# TeensyLED_15041702.net
KiCad netlist of a schematic drawn in EAGLE
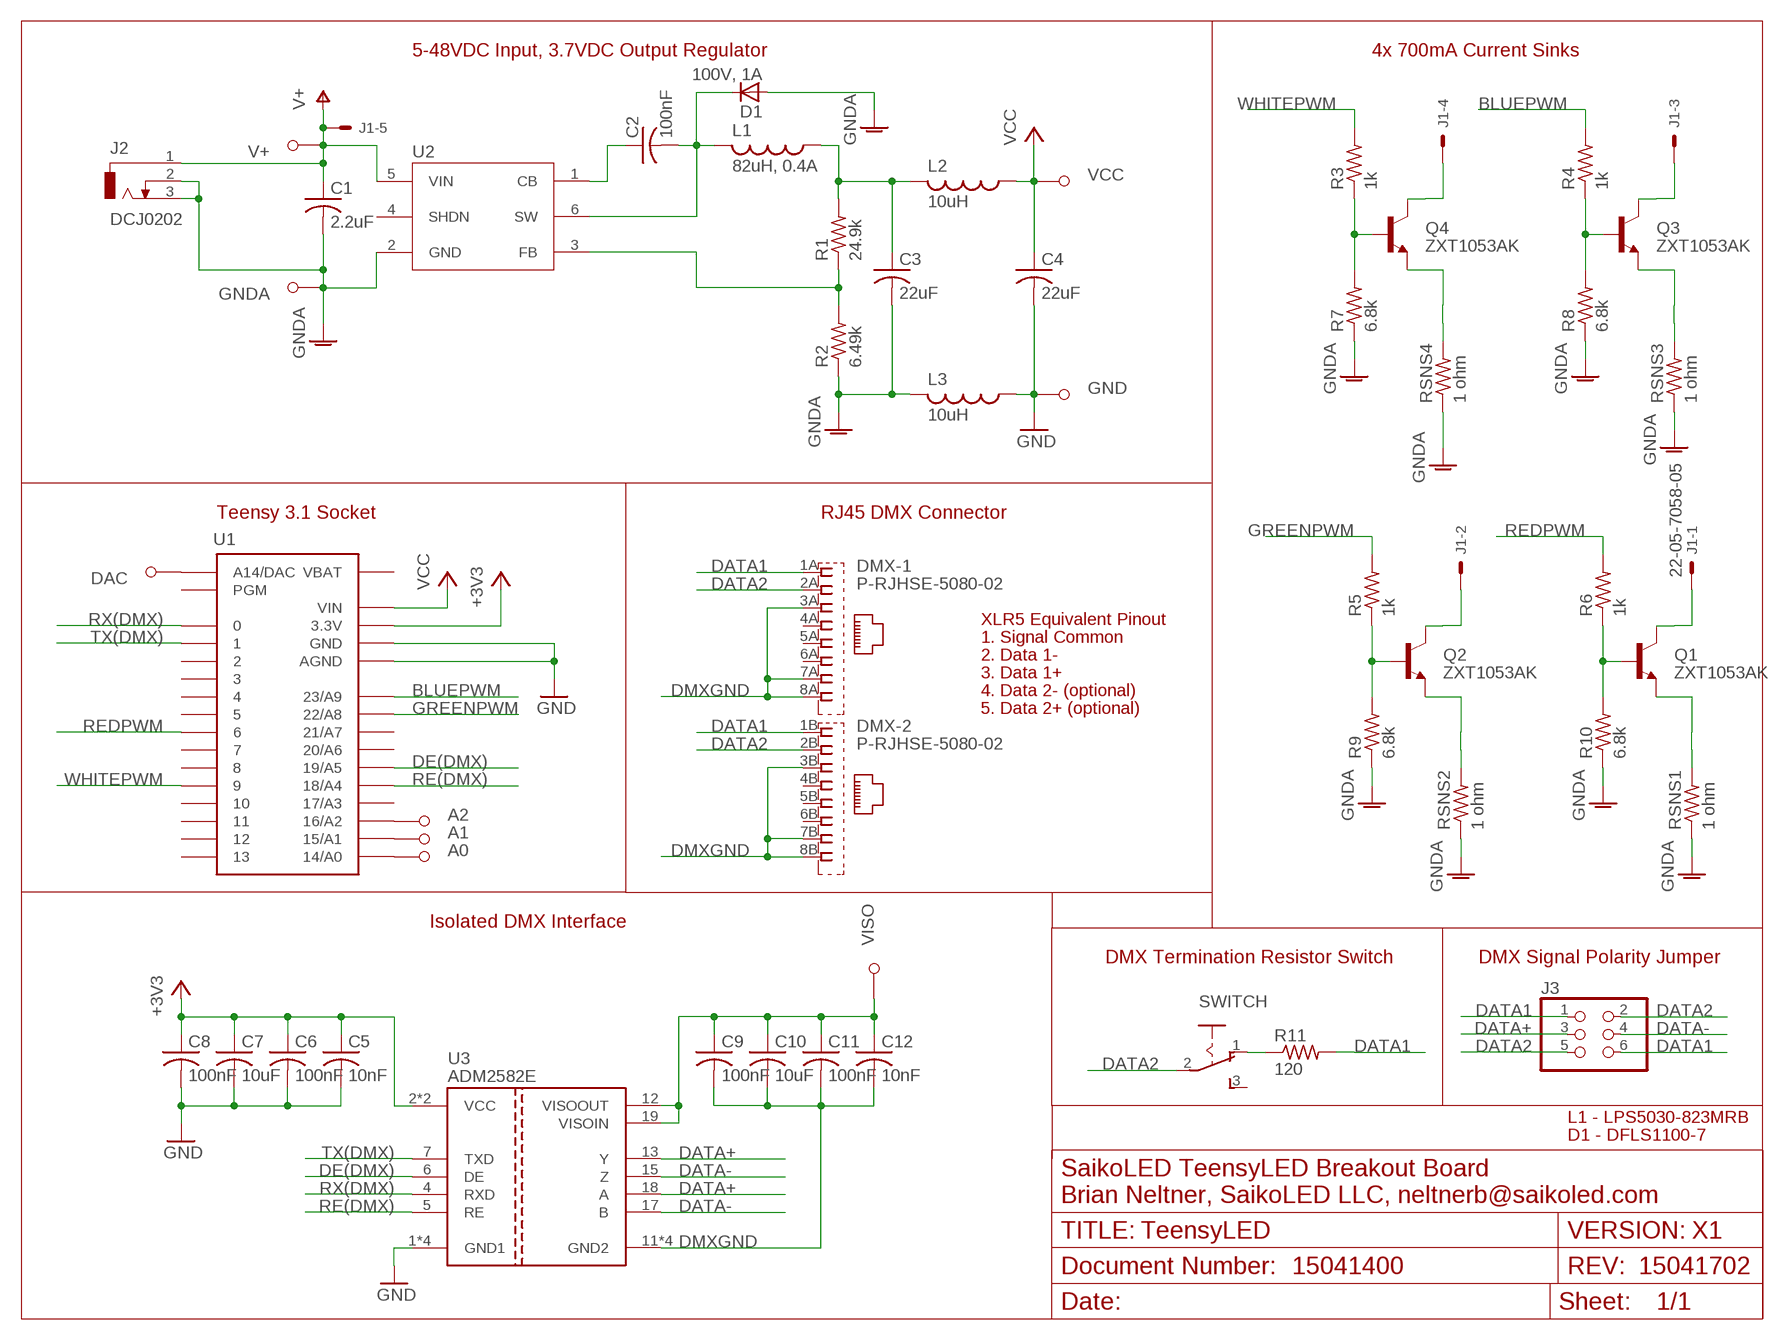
[diagram p0: schematic, sheet 1]

(export (version "E")
  (design (tool "Eeschema 10.0.6"))
  (components
    (comp (ref "A0")
      (value "5016")
      (footprint "eagle-import:5016")
      (libsource (lib "eagle-import") (part "5016"))
    )
    (comp (ref "A1")
      (value "5016")
      (footprint "eagle-import:5016")
      (libsource (lib "eagle-import") (part "5016"))
    )
    (comp (ref "A2")
      (value "5016")
      (footprint "eagle-import:5016")
      (libsource (lib "eagle-import") (part "5016"))
    )
    (comp (ref "C1")
      (value "2.2uF")
      (footprint "eagle-import:C1210K")
      (libsource (lib "eagle-import") (part "C-USC1210K"))
    )
    (comp (ref "C2")
      (value "100nF")
      (footprint "eagle-import:C0805K")
      (libsource (lib "eagle-import") (part "C-USC0805K"))
    )
    (comp (ref "C3")
      (value "22uF")
      (footprint "eagle-import:C0805K")
      (fields (field (name "MF") "Multicomp Passives") (field (name "MPN") "MCLV4R7M1HB-0513-RH"))
      (libsource (lib "eagle-import") (part "C-USC0805K"))
    )
    (comp (ref "C4")
      (value "22uF")
      (footprint "eagle-import:C0805K")
      (libsource (lib "eagle-import") (part "C-USC0805K"))
    )
    (comp (ref "C5")
      (value "10nF")
      (footprint "eagle-import:C0402PRO")
      (libsource (lib "eagle-import") (part "C-USC0402PRO"))
    )
    (comp (ref "C6")
      (value "100nF")
      (footprint "eagle-import:C0402PRO")
      (libsource (lib "eagle-import") (part "C-USC0402PRO"))
    )
    (comp (ref "C7")
      (value "10uF")
      (footprint "eagle-import:C0402PRO")
      (libsource (lib "eagle-import") (part "C-USC0402PRO"))
    )
    (comp (ref "C8")
      (value "100nF")
      (footprint "eagle-import:C0402PRO")
      (libsource (lib "eagle-import") (part "C-USC0402PRO"))
    )
    (comp (ref "C9")
      (value "100nF")
      (footprint "eagle-import:C0402PRO")
      (libsource (lib "eagle-import") (part "C-USC0402PRO"))
    )
    (comp (ref "C10")
      (value "10uF")
      (footprint "eagle-import:C0402PRO")
      (libsource (lib "eagle-import") (part "C-USC0402PRO"))
    )
    (comp (ref "C11")
      (value "100nF")
      (footprint "eagle-import:C0402PRO")
      (libsource (lib "eagle-import") (part "C-USC0402PRO"))
    )
    (comp (ref "C12")
      (value "10nF")
      (footprint "eagle-import:C0402PRO")
      (libsource (lib "eagle-import") (part "C-USC0402PRO"))
    )
    (comp (ref "D1")
      (value "100V, 1A")
      (footprint "eagle-import:DFLS1100")
      (libsource (lib "eagle-import") (part "DFLS1100"))
    )
    (comp (ref "DAC")
      (value "5016")
      (footprint "eagle-import:5016")
      (libsource (lib "eagle-import") (part "5016"))
    )
    (comp (ref "DMX")
      (value "P-RJHSE-5080-02")
      (footprint "eagle-import:P-RJHSE-5080-02")
      (libsource (lib "eagle-import") (part "P-RJHSE-5080-02"))
    )
    (comp (ref "FRAME1")
      (value "LETTER_L")
      (footprint "eagle-import:PCBINFO")
      (libsource (lib "eagle-import") (part "LETTER_L"))
    )
    (comp (ref "GND")
      (value "5016")
      (footprint "eagle-import:5016")
      (libsource (lib "eagle-import") (part "5016"))
    )
    (comp (ref "GNDA")
      (value "5016")
      (footprint "eagle-import:5016")
      (libsource (lib "eagle-import") (part "5016"))
    )
    (comp (ref "J1")
      (value "22-05-7058-05")
      (footprint "eagle-import:7395-05")
      (libsource (lib "eagle-import") (part "22-?-0505-7058"))
    )
    (comp (ref "J2")
      (value "DCJ0202")
      (footprint "eagle-import:DCJ0202")
      (libsource (lib "eagle-import") (part "DCJ0202"))
    )
    (comp (ref "J3")
      (value "PINHD-2X3")
      (footprint "eagle-import:2X03")
      (libsource (lib "eagle-import") (part "PINHD-2X3"))
    )
    (comp (ref "L1")
      (value "82uH, 0.4A")
      (footprint "eagle-import:LPS5030")
      (libsource (lib "eagle-import") (part "L-US"))
    )
    (comp (ref "L2")
      (value "10uH")
      (footprint "eagle-import:L2012C")
      (libsource (lib "eagle-import") (part "rcl_L-USL2012C"))
    )
    (comp (ref "L3")
      (value "10uH")
      (footprint "eagle-import:L2012C")
      (libsource (lib "eagle-import") (part "rcl_L-USL2012C"))
    )
    (comp (ref "Q1")
      (value "ZXT1053AK")
      (footprint "eagle-import:TO252")
      (libsource (lib "eagle-import") (part "ZXT1053AK"))
    )
    (comp (ref "Q2")
      (value "ZXT1053AK")
      (footprint "eagle-import:TO252")
      (libsource (lib "eagle-import") (part "ZXT1053AK"))
    )
    (comp (ref "Q3")
      (value "ZXT1053AK")
      (footprint "eagle-import:TO252")
      (libsource (lib "eagle-import") (part "ZXT1053AK"))
    )
    (comp (ref "Q4")
      (value "ZXT1053AK")
      (footprint "eagle-import:TO252")
      (libsource (lib "eagle-import") (part "ZXT1053AK"))
    )
    (comp (ref "R1")
      (value "24.9k")
      (footprint "eagle-import:R0402PRO")
      (fields (field (name "MPN") "BLU0402-9762-BT25W"))
      (libsource (lib "eagle-import") (part "R-US_R0402PRO"))
    )
    (comp (ref "R2")
      (value "6.49k")
      (footprint "eagle-import:R0402PRO")
      (fields (field (name "MPN") "ERJ-3EKF4123V"))
      (libsource (lib "eagle-import") (part "R-US_R0402PRO"))
    )
    (comp (ref "R3")
      (value "1k")
      (footprint "eagle-import:R0402PRO")
      (libsource (lib "eagle-import") (part "R-US_R0402PRO"))
    )
    (comp (ref "R4")
      (value "1k")
      (footprint "eagle-import:R0402PRO")
      (libsource (lib "eagle-import") (part "R-US_R0402PRO"))
    )
    (comp (ref "R5")
      (value "1k")
      (footprint "eagle-import:R0402PRO")
      (libsource (lib "eagle-import") (part "R-US_R0402PRO"))
    )
    (comp (ref "R6")
      (value "1k")
      (footprint "eagle-import:R0402PRO")
      (libsource (lib "eagle-import") (part "R-US_R0402PRO"))
    )
    (comp (ref "R7")
      (value "6.8k")
      (footprint "eagle-import:R0402PRO")
      (libsource (lib "eagle-import") (part "R-US_R0402PRO"))
    )
    (comp (ref "R8")
      (value "6.8k")
      (footprint "eagle-import:R0402PRO")
      (libsource (lib "eagle-import") (part "R-US_R0402PRO"))
    )
    (comp (ref "R9")
      (value "6.8k")
      (footprint "eagle-import:R0402PRO")
      (libsource (lib "eagle-import") (part "R-US_R0402PRO"))
    )
    (comp (ref "R10")
      (value "6.8k")
      (footprint "eagle-import:R0402PRO")
      (libsource (lib "eagle-import") (part "R-US_R0402PRO"))
    )
    (comp (ref "R11")
      (value "120")
      (footprint "eagle-import:R0402PRO")
      (libsource (lib "eagle-import") (part "R-US_R0402PRO"))
    )
    (comp (ref "RSNS1")
      (value "1 ohm")
      (footprint "eagle-import:R1206")
      (libsource (lib "eagle-import") (part "R-US_R1206"))
    )
    (comp (ref "RSNS2")
      (value "1 ohm")
      (footprint "eagle-import:R1206")
      (libsource (lib "eagle-import") (part "R-US_R1206"))
    )
    (comp (ref "RSNS3")
      (value "1 ohm")
      (footprint "eagle-import:R1206")
      (libsource (lib "eagle-import") (part "R-US_R1206"))
    )
    (comp (ref "RSNS4")
      (value "1 ohm")
      (footprint "eagle-import:R1206")
      (libsource (lib "eagle-import") (part "R-US_R1206"))
    )
    (comp (ref "SWITCH")
      (value "M251")
      (footprint "eagle-import:SK-12F17-G")
      (libsource (lib "eagle-import") (part "M251"))
    )
    (comp (ref "U1")
      (value "TEENSY_3.0_BASIC")
      (footprint "eagle-import:TEENSY_3.0_BASIC")
      (libsource (lib "eagle-import") (part "TEENSY_3.0_BASIC"))
    )
    (comp (ref "U2")
      (value "LMR16006YDDCT")
      (footprint "eagle-import:DDC0006A")
      (fields
        (field (name "MANUFACTURER") "Texas Instruments")
        (field (name "PARTNUMBER") "LMR16006YDDC")
        (field (name "MF") "FARNELL")
      )
      (libsource (lib "eagle-import") (part "LMR16006YDDCT"))
    )
    (comp (ref "U3")
      (value "ADM2582E")
      (footprint "eagle-import:SO-20DW")
      (libsource (lib "eagle-import") (part "ADM2582E"))
    )
    (comp (ref "V+")
      (value "5016")
      (footprint "eagle-import:5016")
      (libsource (lib "eagle-import") (part "5016"))
    )
    (comp (ref "VCC")
      (value "5016")
      (footprint "eagle-import:5016")
      (libsource (lib "eagle-import") (part "5016"))
    )
    (comp (ref "VISO")
      (value "5016")
      (footprint "eagle-import:5016")
      (libsource (lib "eagle-import") (part "5016"))
    )
  )
  (nets
    (net (code "1") (name "+3V3") (class "Default")
      (node (ref "C5") (pin "1") (pinfunction "1_1") (pintype "passive"))
      (node (ref "C6") (pin "1") (pinfunction "1_1") (pintype "passive"))
      (node (ref "C7") (pin "1") (pinfunction "1_1") (pintype "passive"))
      (node (ref "C8") (pin "1") (pinfunction "1_1") (pintype "passive"))
      (node (ref "U1") (pin "3.3V") (pinfunction "3.3V_3.3V") (pintype "power_in"))
      (node (ref "U1") (pin "3.3V1") (pinfunction "3.3V_3.3V1") (pintype "power_in"))
      (node (ref "U3") (pin "2") (pinfunction "VCC_2") (pintype "bidirectional"))
      (node (ref "U3") (pin "8") (pinfunction "VCC_8") (pintype "bidirectional"))
    )
    (net (code "2") (name "/BLUEPWM") (class "Default")
      (node (ref "R4") (pin "2") (pinfunction "2_2") (pintype "passive"))
      (node (ref "U1") (pin "23/A9") (pinfunction "23/A9_23/A9") (pintype "bidirectional"))
    )
    (net (code "3") (name "/DATA+") (class "Default")
      (node (ref "J3") (pin "3") (pinfunction "3_3") (pintype "passive"))
      (node (ref "U3") (pin "13") (pinfunction "Y_13") (pintype "bidirectional"))
      (node (ref "U3") (pin "18") (pinfunction "A_18") (pintype "bidirectional"))
    )
    (net (code "4") (name "/DATA-") (class "Default")
      (node (ref "J3") (pin "4") (pinfunction "4_4") (pintype "passive"))
      (node (ref "U3") (pin "15") (pinfunction "Z_15") (pintype "bidirectional"))
      (node (ref "U3") (pin "17") (pinfunction "B_17") (pintype "bidirectional"))
    )
    (net (code "5") (name "/DATA1") (class "Default")
      (node (ref "DMX") (pin "1A") (pinfunction "1_1A") (pintype "passive"))
      (node (ref "DMX") (pin "1B") (pinfunction "1_1B") (pintype "passive"))
      (node (ref "J3") (pin "1") (pinfunction "1_1") (pintype "passive"))
      (node (ref "J3") (pin "6") (pinfunction "6_6") (pintype "passive"))
      (node (ref "R11") (pin "2") (pinfunction "2_2") (pintype "passive"))
    )
    (net (code "6") (name "/DATA2") (class "Default")
      (node (ref "DMX") (pin "2A") (pinfunction "2_2A") (pintype "passive"))
      (node (ref "DMX") (pin "2B") (pinfunction "2_2B") (pintype "passive"))
      (node (ref "J3") (pin "2") (pinfunction "2_2") (pintype "passive"))
      (node (ref "J3") (pin "5") (pinfunction "5_5") (pintype "passive"))
      (node (ref "SWITCH") (pin "2") (pinfunction "P_2") (pintype "passive"))
    )
    (net (code "7") (name "/DE(DMX)") (class "Default")
      (node (ref "U1") (pin "19/A5") (pinfunction "19/A5_19/A5") (pintype "bidirectional"))
      (node (ref "U3") (pin "6") (pinfunction "DE_6") (pintype "bidirectional"))
    )
    (net (code "8") (name "/DMXGND") (class "Default")
      (node (ref "C10") (pin "2") (pinfunction "2_2") (pintype "passive"))
      (node (ref "C11") (pin "2") (pinfunction "2_2") (pintype "passive"))
      (node (ref "C12") (pin "2") (pinfunction "2_2") (pintype "passive"))
      (node (ref "C9") (pin "2") (pinfunction "2_2") (pintype "passive"))
      (node (ref "DMX") (pin "3A") (pinfunction "3_3A") (pintype "passive"))
      (node (ref "DMX") (pin "3B") (pinfunction "3_3B") (pintype "passive"))
      (node (ref "DMX") (pin "7A") (pinfunction "7_7A") (pintype "passive"))
      (node (ref "DMX") (pin "7B") (pinfunction "7_7B") (pintype "passive"))
      (node (ref "DMX") (pin "8A") (pinfunction "8_8A") (pintype "passive"))
      (node (ref "DMX") (pin "8B") (pinfunction "8_8B") (pintype "passive"))
      (node (ref "U3") (pin "11") (pinfunction "GND2_11") (pintype "bidirectional"))
      (node (ref "U3") (pin "14") (pinfunction "GND2_14") (pintype "bidirectional"))
      (node (ref "U3") (pin "16") (pinfunction "GND2_16") (pintype "bidirectional"))
      (node (ref "U3") (pin "20") (pinfunction "GND2_20") (pintype "bidirectional"))
    )
    (net (code "9") (name "/GREENPWM") (class "Default")
      (node (ref "R5") (pin "2") (pinfunction "2_2") (pintype "passive"))
      (node (ref "U1") (pin "22/A8") (pinfunction "22/A8_22/A8") (pintype "bidirectional"))
    )
    (net (code "10") (name "/RE(DMX)") (class "Default")
      (node (ref "U1") (pin "18/A4") (pinfunction "18/A4_18/A4") (pintype "bidirectional"))
      (node (ref "U3") (pin "5") (pinfunction "RE_5") (pintype "bidirectional"))
    )
    (net (code "11") (name "/REDPWM") (class "Default")
      (node (ref "R6") (pin "2") (pinfunction "2_2") (pintype "passive"))
      (node (ref "U1") (pin "6") (pinfunction "6_6") (pintype "bidirectional"))
    )
    (net (code "12") (name "/RX(DMX)") (class "Default")
      (node (ref "U1") (pin "0") (pinfunction "0_0") (pintype "bidirectional"))
      (node (ref "U3") (pin "4") (pinfunction "RXD_4") (pintype "bidirectional"))
    )
    (net (code "13") (name "/TX(DMX)") (class "Default")
      (node (ref "U1") (pin "1") (pinfunction "1_1") (pintype "bidirectional"))
      (node (ref "U3") (pin "7") (pinfunction "TXD_7") (pintype "bidirectional"))
    )
    (net (code "14") (name "/VBAT") (class "Default")
      (node (ref "U1") (pin "VBAT") (pinfunction "VBAT_VBAT") (pintype "power_in"))
    )
    (net (code "15") (name "/WHITEPWM") (class "Default")
      (node (ref "R3") (pin "2") (pinfunction "2_2") (pintype "passive"))
      (node (ref "U1") (pin "9") (pinfunction "9_9") (pintype "bidirectional"))
    )
    (net (code "16") (name "GND") (class "Default")
      (node (ref "C4") (pin "2") (pinfunction "2_2") (pintype "passive"))
      (node (ref "C5") (pin "2") (pinfunction "2_2") (pintype "passive"))
      (node (ref "C6") (pin "2") (pinfunction "2_2") (pintype "passive"))
      (node (ref "C7") (pin "2") (pinfunction "2_2") (pintype "passive"))
      (node (ref "C8") (pin "2") (pinfunction "2_2") (pintype "passive"))
      (node (ref "GND") (pin "P$1") (pinfunction "P$1_P$1") (pintype "passive"))
      (node (ref "L3") (pin "1") (pinfunction "1_1") (pintype "passive"))
      (node (ref "U1") (pin "AGND") (pinfunction "AGND_AGND") (pintype "power_in"))
      (node (ref "U1") (pin "GND") (pinfunction "GND_GND") (pintype "power_in"))
      (node (ref "U1") (pin "GND1") (pinfunction "GND_GND1") (pintype "power_in"))
      (node (ref "U3") (pin "1") (pinfunction "GND1_1") (pintype "bidirectional"))
      (node (ref "U3") (pin "10") (pinfunction "GND1_10") (pintype "bidirectional"))
      (node (ref "U3") (pin "3") (pinfunction "GND1_3") (pintype "bidirectional"))
      (node (ref "U3") (pin "9") (pinfunction "GND1_9") (pintype "bidirectional"))
    )
    (net (code "17") (name "GNDA") (class "Default")
      (node (ref "C1") (pin "2") (pinfunction "2_2") (pintype "passive"))
      (node (ref "C3") (pin "2") (pinfunction "2_2") (pintype "passive"))
      (node (ref "D1") (pin "A") (pinfunction "A_A") (pintype "passive"))
      (node (ref "GNDA") (pin "P$1") (pinfunction "P$1_P$1") (pintype "passive"))
      (node (ref "J2") (pin "2") (pinfunction "2_2") (pintype "passive"))
      (node (ref "J2") (pin "3") (pinfunction "3_3") (pintype "passive"))
      (node (ref "L3") (pin "2") (pinfunction "2_2") (pintype "passive"))
      (node (ref "R10") (pin "1") (pinfunction "1_1") (pintype "passive"))
      (node (ref "R2") (pin "1") (pinfunction "1_1") (pintype "passive"))
      (node (ref "R7") (pin "1") (pinfunction "1_1") (pintype "passive"))
      (node (ref "R8") (pin "1") (pinfunction "1_1") (pintype "passive"))
      (node (ref "R9") (pin "1") (pinfunction "1_1") (pintype "passive"))
      (node (ref "RSNS1") (pin "1") (pinfunction "1_1") (pintype "passive"))
      (node (ref "RSNS2") (pin "1") (pinfunction "1_1") (pintype "passive"))
      (node (ref "RSNS3") (pin "1") (pinfunction "1_1") (pintype "passive"))
      (node (ref "RSNS4") (pin "1") (pinfunction "1_1") (pintype "passive"))
      (node (ref "U2") (pin "2") (pinfunction "GND_2") (pintype "power_in"))
    )
    (net (code "18") (name "Net-(A0-PadP$1)") (class "Default")
      (node (ref "A0") (pin "P$1") (pinfunction "P$1_P$1") (pintype "passive"))
      (node (ref "U1") (pin "14/A0") (pinfunction "14/A0_14/A0") (pintype "bidirectional"))
    )
    (net (code "19") (name "Net-(A1-PadP$1)") (class "Default")
      (node (ref "A1") (pin "P$1") (pinfunction "P$1_P$1") (pintype "passive"))
      (node (ref "U1") (pin "15/A1") (pinfunction "15/A1_15/A1") (pintype "bidirectional"))
    )
    (net (code "20") (name "Net-(A2-PadP$1)") (class "Default")
      (node (ref "A2") (pin "P$1") (pinfunction "P$1_P$1") (pintype "passive"))
      (node (ref "U1") (pin "16/A2") (pinfunction "16/A2_16/A2") (pintype "bidirectional"))
    )
    (net (code "21") (name "Net-(J1A-S)") (class "Default")
      (node (ref "J1") (pin "1") (pinfunction "S_1") (pintype "passive"))
      (node (ref "Q1") (pin "C") (pinfunction "C_C") (pintype "passive"))
    )
    (net (code "22") (name "Net-(J1B-S)") (class "Default")
      (node (ref "J1") (pin "2") (pinfunction "S_2") (pintype "passive"))
      (node (ref "Q2") (pin "C") (pinfunction "C_C") (pintype "passive"))
    )
    (net (code "23") (name "Net-(J1C-S)") (class "Default")
      (node (ref "J1") (pin "3") (pinfunction "S_3") (pintype "passive"))
      (node (ref "Q3") (pin "C") (pinfunction "C_C") (pintype "passive"))
    )
    (net (code "24") (name "Net-(J1D-S)") (class "Default")
      (node (ref "J1") (pin "4") (pinfunction "S_4") (pintype "passive"))
      (node (ref "Q4") (pin "C") (pinfunction "C_C") (pintype "passive"))
    )
    (net (code "25") (name "Net-(L1-1)") (class "Default")
      (node (ref "C3") (pin "1") (pinfunction "1_1") (pintype "passive"))
      (node (ref "L1") (pin "P$1") (pinfunction "1_P$1") (pintype "passive"))
      (node (ref "L2") (pin "2") (pinfunction "2_2") (pintype "passive"))
      (node (ref "R1") (pin "2") (pinfunction "2_2") (pintype "passive"))
    )
    (net (code "26") (name "Net-(L1-2)") (class "Default")
      (node (ref "C2") (pin "2") (pinfunction "2_2") (pintype "passive"))
      (node (ref "D1") (pin "C") (pinfunction "C_C") (pintype "passive"))
      (node (ref "L1") (pin "P$2") (pinfunction "2_P$2") (pintype "passive"))
      (node (ref "U2") (pin "6") (pinfunction "SW_6") (pintype "power_in"))
    )
    (net (code "27") (name "Net-(Q1-PadB)") (class "Default")
      (node (ref "Q1") (pin "B") (pinfunction "B_B") (pintype "passive"))
      (node (ref "R10") (pin "2") (pinfunction "2_2") (pintype "passive"))
      (node (ref "R6") (pin "1") (pinfunction "1_1") (pintype "passive"))
    )
    (net (code "28") (name "Net-(Q1-PadE)") (class "Default")
      (node (ref "Q1") (pin "E") (pinfunction "E_E") (pintype "passive"))
      (node (ref "RSNS1") (pin "2") (pinfunction "2_2") (pintype "passive"))
    )
    (net (code "29") (name "Net-(Q2-PadB)") (class "Default")
      (node (ref "Q2") (pin "B") (pinfunction "B_B") (pintype "passive"))
      (node (ref "R5") (pin "1") (pinfunction "1_1") (pintype "passive"))
      (node (ref "R9") (pin "2") (pinfunction "2_2") (pintype "passive"))
    )
    (net (code "30") (name "Net-(Q2-PadE)") (class "Default")
      (node (ref "Q2") (pin "E") (pinfunction "E_E") (pintype "passive"))
      (node (ref "RSNS2") (pin "2") (pinfunction "2_2") (pintype "passive"))
    )
    (net (code "31") (name "Net-(Q3-PadB)") (class "Default")
      (node (ref "Q3") (pin "B") (pinfunction "B_B") (pintype "passive"))
      (node (ref "R4") (pin "1") (pinfunction "1_1") (pintype "passive"))
      (node (ref "R8") (pin "2") (pinfunction "2_2") (pintype "passive"))
    )
    (net (code "32") (name "Net-(Q3-PadE)") (class "Default")
      (node (ref "Q3") (pin "E") (pinfunction "E_E") (pintype "passive"))
      (node (ref "RSNS3") (pin "2") (pinfunction "2_2") (pintype "passive"))
    )
    (net (code "33") (name "Net-(Q4-PadB)") (class "Default")
      (node (ref "Q4") (pin "B") (pinfunction "B_B") (pintype "passive"))
      (node (ref "R3") (pin "1") (pinfunction "1_1") (pintype "passive"))
      (node (ref "R7") (pin "2") (pinfunction "2_2") (pintype "passive"))
    )
    (net (code "34") (name "Net-(Q4-PadE)") (class "Default")
      (node (ref "Q4") (pin "E") (pinfunction "E_E") (pintype "passive"))
      (node (ref "RSNS4") (pin "2") (pinfunction "2_2") (pintype "passive"))
    )
    (net (code "35") (name "Net-(SWITCH-O)") (class "Default")
      (node (ref "R11") (pin "1") (pinfunction "1_1") (pintype "passive"))
      (node (ref "SWITCH") (pin "1") (pinfunction "O_1") (pintype "passive"))
    )
    (net (code "36") (name "Net-(U1-A14{slash}DAC)") (class "Default")
      (node (ref "DAC") (pin "P$1") (pinfunction "P$1_P$1") (pintype "passive"))
      (node (ref "U1") (pin "RESET") (pinfunction "A14/DAC_RESET") (pintype "bidirectional"))
    )
    (net (code "37") (name "Net-(U2-CB)") (class "Default")
      (node (ref "C2") (pin "1") (pinfunction "1_1") (pintype "passive"))
      (node (ref "U2") (pin "1") (pinfunction "CB_1") (pintype "output"))
    )
    (net (code "38") (name "Net-(U2-FB)") (class "Default")
      (node (ref "R1") (pin "1") (pinfunction "1_1") (pintype "passive"))
      (node (ref "R2") (pin "2") (pinfunction "2_2") (pintype "passive"))
      (node (ref "U2") (pin "3") (pinfunction "FB_3") (pintype "input"))
    )
    (net (code "39") (name "Net-(U3-VISOIN)") (class "Default")
      (node (ref "C10") (pin "1") (pinfunction "1_1") (pintype "passive"))
      (node (ref "C11") (pin "1") (pinfunction "1_1") (pintype "passive"))
      (node (ref "C12") (pin "1") (pinfunction "1_1") (pintype "passive"))
      (node (ref "C9") (pin "1") (pinfunction "1_1") (pintype "passive"))
      (node (ref "U3") (pin "12") (pinfunction "VISOOUT_12") (pintype "bidirectional"))
      (node (ref "U3") (pin "19") (pinfunction "VISOIN_19") (pintype "bidirectional"))
      (node (ref "VISO") (pin "P$1") (pinfunction "P$1_P$1") (pintype "passive"))
    )
    (net (code "40") (name "V+") (class "Default")
      (node (ref "C1") (pin "1") (pinfunction "1_1") (pintype "passive"))
      (node (ref "J1") (pin "5") (pinfunction "S_5") (pintype "passive"))
      (node (ref "J2") (pin "1") (pinfunction "1_1") (pintype "passive"))
      (node (ref "U2") (pin "5") (pinfunction "VIN_5") (pintype "power_in"))
      (node (ref "V+") (pin "P$1") (pinfunction "P$1_P$1") (pintype "passive"))
    )
    (net (code "41") (name "VCC") (class "Default")
      (node (ref "C4") (pin "1") (pinfunction "1_1") (pintype "passive"))
      (node (ref "L2") (pin "1") (pinfunction "1_1") (pintype "passive"))
      (node (ref "U1") (pin "VIN") (pinfunction "VIN_VIN") (pintype "power_in"))
      (node (ref "VCC") (pin "P$1") (pinfunction "P$1_P$1") (pintype "passive"))
    )
    (net (code "42") (name "unconnected-(DMXA-4-Pad4A)") (class "Default")
      (node (ref "DMX") (pin "4A") (pinfunction "4_4A") (pintype "passive"))
    )
    (net (code "43") (name "unconnected-(DMXA-5-Pad5A)") (class "Default")
      (node (ref "DMX") (pin "5A") (pinfunction "5_5A") (pintype "passive"))
    )
    (net (code "44") (name "unconnected-(DMXA-6-Pad6A)") (class "Default")
      (node (ref "DMX") (pin "6A") (pinfunction "6_6A") (pintype "passive"))
    )
    (net (code "45") (name "unconnected-(DMXB-4-Pad4B)") (class "Default")
      (node (ref "DMX") (pin "4B") (pinfunction "4_4B") (pintype "passive"))
    )
    (net (code "46") (name "unconnected-(DMXB-5-Pad5B)") (class "Default")
      (node (ref "DMX") (pin "5B") (pinfunction "5_5B") (pintype "passive"))
    )
    (net (code "47") (name "unconnected-(DMXB-6-Pad6B)") (class "Default")
      (node (ref "DMX") (pin "6B") (pinfunction "6_6B") (pintype "passive"))
    )
    (net (code "48") (name "unconnected-(SWITCH-S-Pad3)") (class "Default")
      (node (ref "SWITCH") (pin "3") (pinfunction "S_3") (pintype "passive"))
    )
    (net (code "49") (name "unconnected-(U1-Pad2)") (class "Default")
      (node (ref "U1") (pin "2") (pinfunction "2_2") (pintype "bidirectional"))
    )
    (net (code "50") (name "unconnected-(U1-Pad3)") (class "Default")
      (node (ref "U1") (pin "3") (pinfunction "3_3") (pintype "bidirectional"))
    )
    (net (code "51") (name "unconnected-(U1-Pad4)") (class "Default")
      (node (ref "U1") (pin "4") (pinfunction "4_4") (pintype "bidirectional"))
    )
    (net (code "52") (name "unconnected-(U1-Pad5)") (class "Default")
      (node (ref "U1") (pin "5") (pinfunction "5_5") (pintype "bidirectional"))
    )
    (net (code "53") (name "unconnected-(U1-Pad7)") (class "Default")
      (node (ref "U1") (pin "7") (pinfunction "7_7") (pintype "bidirectional"))
    )
    (net (code "54") (name "unconnected-(U1-Pad8)") (class "Default")
      (node (ref "U1") (pin "8") (pinfunction "8_8") (pintype "bidirectional"))
    )
    (net (code "55") (name "unconnected-(U1-Pad10)") (class "Default")
      (node (ref "U1") (pin "10") (pinfunction "10_10") (pintype "bidirectional"))
    )
    (net (code "56") (name "unconnected-(U1-Pad11)") (class "Default")
      (node (ref "U1") (pin "11") (pinfunction "11_11") (pintype "bidirectional"))
    )
    (net (code "57") (name "unconnected-(U1-Pad12)") (class "Default")
      (node (ref "U1") (pin "12") (pinfunction "12_12") (pintype "bidirectional"))
    )
    (net (code "58") (name "unconnected-(U1-Pad13)") (class "Default")
      (node (ref "U1") (pin "13") (pinfunction "13_13") (pintype "bidirectional"))
    )
    (net (code "59") (name "unconnected-(U1-Pad17{slash}A3)") (class "Default")
      (node (ref "U1") (pin "17/A3") (pinfunction "17/A3_17/A3") (pintype "bidirectional"))
    )
    (net (code "60") (name "unconnected-(U1-Pad20{slash}A6)") (class "Default")
      (node (ref "U1") (pin "20/A6") (pinfunction "20/A6_20/A6") (pintype "bidirectional"))
    )
    (net (code "61") (name "unconnected-(U1-Pad21{slash}A7)") (class "Default")
      (node (ref "U1") (pin "21/A7") (pinfunction "21/A7_21/A7") (pintype "bidirectional"))
    )
    (net (code "62") (name "unconnected-(U1-PadPGM)") (class "Default")
      (node (ref "U1") (pin "PGM") (pinfunction "PGM_PGM") (pintype "bidirectional"))
    )
    (net (code "63") (name "unconnected-(U2-SHDN-Pad4)") (class "Default")
      (node (ref "U2") (pin "4") (pinfunction "SHDN_4") (pintype "input"))
    )
  )
)
